# EM4095_base_circuit.net
KiCad netlist of a schematic drawn in EAGLE
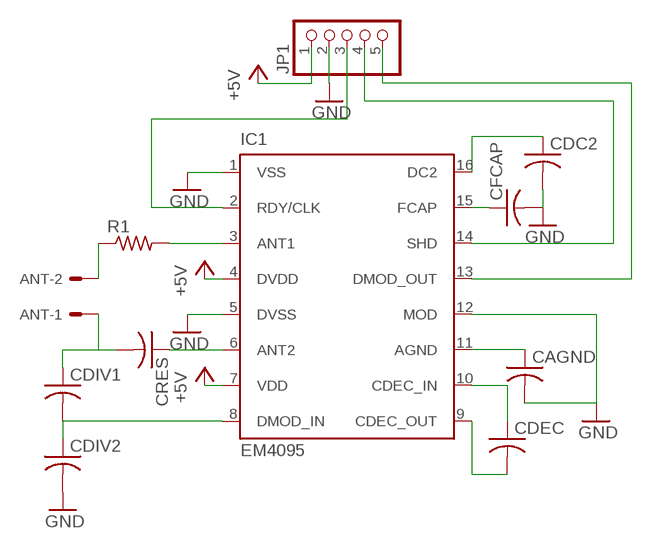
[diagram p0: schematic, sheet 1]

(export (version "E")
  (design (tool "Eeschema 10.0.6"))
  (components
    (comp (ref "ANT")
      (value "KK-156-2")
      (footprint "eagle-import:KK-156-2")
      (libsource (lib "eagle-import") (part "KK-156-2"))
    )
    (comp (ref "CAGND")
      (value "C-USC1206K")
      (footprint "eagle-import:C1206K")
      (libsource (lib "eagle-import") (part "C-USC1206K"))
    )
    (comp (ref "CDC2")
      (value "C-USC1206K")
      (footprint "eagle-import:C1206K")
      (libsource (lib "eagle-import") (part "C-USC1206K"))
    )
    (comp (ref "CDEC")
      (value "C-USC1206K")
      (footprint "eagle-import:C1206K")
      (libsource (lib "eagle-import") (part "C-USC1206K"))
    )
    (comp (ref "CDIV1")
      (value "C-USC1206K")
      (footprint "eagle-import:C1206K")
      (libsource (lib "eagle-import") (part "C-USC1206K"))
    )
    (comp (ref "CDIV2")
      (value "C-USC1206K")
      (footprint "eagle-import:C1206K")
      (libsource (lib "eagle-import") (part "C-USC1206K"))
    )
    (comp (ref "CFCAP")
      (value "C-USC1206K")
      (footprint "eagle-import:C1206K")
      (libsource (lib "eagle-import") (part "C-USC1206K"))
    )
    (comp (ref "CRES")
      (value "C-USC1206K")
      (footprint "eagle-import:C1206K")
      (libsource (lib "eagle-import") (part "C-USC1206K"))
    )
    (comp (ref "IC1")
      (value "EM4095")
      (footprint "eagle-import:SO16")
      (libsource (lib "eagle-import") (part "EM4095"))
    )
    (comp (ref "JP1")
      (value "PINHD-1X5")
      (footprint "eagle-import:1X05")
      (libsource (lib "eagle-import") (part "PINHD-1X5"))
    )
    (comp (ref "R1")
      (value "R-US_R1206")
      (footprint "eagle-import:R1206")
      (libsource (lib "eagle-import") (part "R-US_R1206"))
    )
  )
  (nets
    (net (code "1") (name "+5V") (class "Default")
      (node (ref "IC1") (pin "4") (pinfunction "DVDD_4") (pintype "power_in"))
      (node (ref "IC1") (pin "7") (pinfunction "VDD_7") (pintype "power_in"))
      (node (ref "JP1") (pin "1") (pinfunction "1_1") (pintype "passive"))
    )
    (net (code "2") (name "GND") (class "Default")
      (node (ref "CAGND") (pin "2") (pinfunction "2_2") (pintype "passive"))
      (node (ref "CDC2") (pin "2") (pinfunction "2_2") (pintype "passive"))
      (node (ref "CDIV2") (pin "2") (pinfunction "2_2") (pintype "passive"))
      (node (ref "CFCAP") (pin "2") (pinfunction "2_2") (pintype "passive"))
      (node (ref "IC1") (pin "1") (pinfunction "VSS_1") (pintype "power_in"))
      (node (ref "IC1") (pin "12") (pinfunction "MOD_12") (pintype "input"))
      (node (ref "IC1") (pin "5") (pinfunction "DVSS_5") (pintype "power_in"))
      (node (ref "JP1") (pin "2") (pinfunction "2_2") (pintype "passive"))
    )
    (net (code "3") (name "Net-(ANTA-S)") (class "Default")
      (node (ref "ANT") (pin "1") (pinfunction "S_1") (pintype "passive"))
      (node (ref "CDIV1") (pin "1") (pinfunction "1_1") (pintype "passive"))
      (node (ref "CRES") (pin "2") (pinfunction "2_2") (pintype "passive"))
    )
    (net (code "4") (name "Net-(ANTB-S)") (class "Default")
      (node (ref "ANT") (pin "2") (pinfunction "S_2") (pintype "passive"))
      (node (ref "R1") (pin "1") (pinfunction "1_1") (pintype "passive"))
    )
    (net (code "5") (name "Net-(IC1-AGND)") (class "Default")
      (node (ref "CAGND") (pin "1") (pinfunction "1_1") (pintype "passive"))
      (node (ref "IC1") (pin "11") (pinfunction "AGND_11") (pintype "power_in"))
    )
    (net (code "6") (name "Net-(IC1-ANT1)") (class "Default")
      (node (ref "IC1") (pin "3") (pinfunction "ANT1_3") (pintype "passive"))
      (node (ref "R1") (pin "2") (pinfunction "2_2") (pintype "passive"))
    )
    (net (code "7") (name "Net-(IC1-ANT2)") (class "Default")
      (node (ref "CRES") (pin "1") (pinfunction "1_1") (pintype "passive"))
      (node (ref "IC1") (pin "6") (pinfunction "ANT2_6") (pintype "passive"))
    )
    (net (code "8") (name "Net-(IC1-CDEC_IN)") (class "Default")
      (node (ref "CDEC") (pin "1") (pinfunction "1_1") (pintype "passive"))
      (node (ref "IC1") (pin "10") (pinfunction "CDEC_IN_10") (pintype "input"))
    )
    (net (code "9") (name "Net-(IC1-CDEC_OUT)") (class "Default")
      (node (ref "CDEC") (pin "2") (pinfunction "2_2") (pintype "passive"))
      (node (ref "IC1") (pin "9") (pinfunction "CDEC_OUT_9") (pintype "output"))
    )
    (net (code "10") (name "Net-(IC1-DC2)") (class "Default")
      (node (ref "CDC2") (pin "1") (pinfunction "1_1") (pintype "passive"))
      (node (ref "IC1") (pin "16") (pinfunction "DC2_16") (pintype "passive"))
    )
    (net (code "11") (name "Net-(IC1-DMOD_IN)") (class "Default")
      (node (ref "CDIV1") (pin "2") (pinfunction "2_2") (pintype "passive"))
      (node (ref "CDIV2") (pin "1") (pinfunction "1_1") (pintype "passive"))
      (node (ref "IC1") (pin "8") (pinfunction "DMOD_IN_8") (pintype "input"))
    )
    (net (code "12") (name "Net-(IC1-DMOD_OUT)") (class "Default")
      (node (ref "IC1") (pin "13") (pinfunction "DMOD_OUT_13") (pintype "output"))
      (node (ref "JP1") (pin "5") (pinfunction "5_5") (pintype "passive"))
    )
    (net (code "13") (name "Net-(IC1-FCAP)") (class "Default")
      (node (ref "CFCAP") (pin "1") (pinfunction "1_1") (pintype "passive"))
      (node (ref "IC1") (pin "15") (pinfunction "FCAP_15") (pintype "passive"))
    )
    (net (code "14") (name "Net-(IC1-RDY{slash}CLK)") (class "Default")
      (node (ref "IC1") (pin "2") (pinfunction "RDY/CLK_2") (pintype "output"))
      (node (ref "JP1") (pin "3") (pinfunction "3_3") (pintype "passive"))
    )
    (net (code "15") (name "Net-(IC1-SHD)") (class "Default")
      (node (ref "IC1") (pin "14") (pinfunction "SHD_14") (pintype "input"))
      (node (ref "JP1") (pin "4") (pinfunction "4_4") (pintype "passive"))
    )
  )
)
